# Schematic.net
KiCad netlist of a schematic drawn in EAGLE
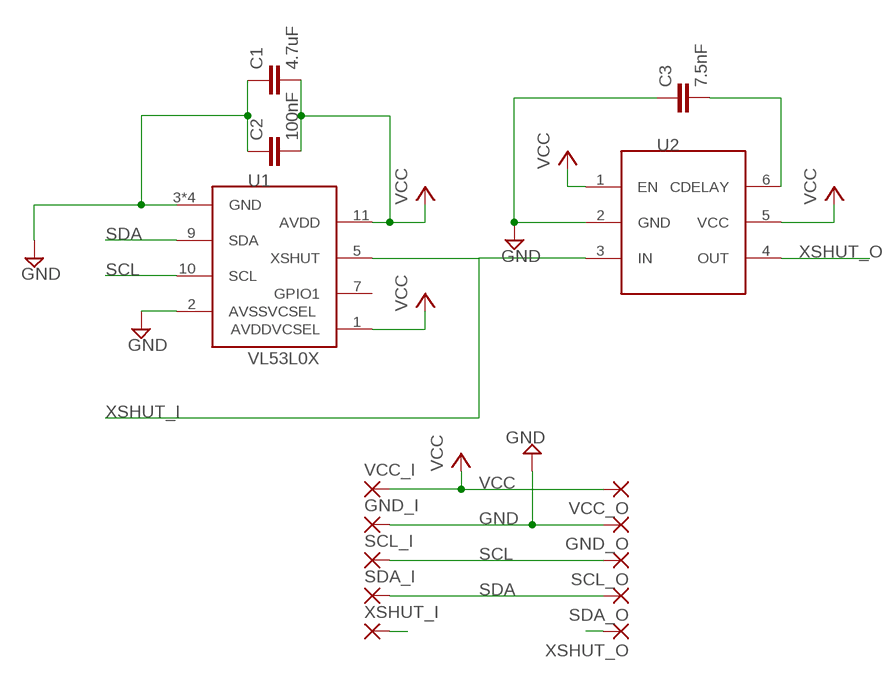
[diagram p0: schematic, sheet 1]

(export (version "E")
  (design (tool "Eeschema 10.0.6"))
  (components
    (comp (ref "C1")
      (value "4.7uF")
      (footprint "eagle-import:0603")
      (libsource (lib "eagle-import") (part "4.7UF0603"))
    )
    (comp (ref "C2")
      (value "100nF")
      (footprint "eagle-import:0603")
      (libsource (lib "eagle-import") (part "0.1UF-0603-25V-5%"))
    )
    (comp (ref "C3")
      (value "7.5nF")
      (footprint "eagle-import:0402")
      (libsource (lib "eagle-import") (part "100PF-0402-50V-5%"))
    )
    (comp (ref "GND_I")
      (value "SMD2")
      (footprint "eagle-import:SMD1,27-2,54")
      (libsource (lib "eagle-import") (part "SMD2"))
    )
    (comp (ref "GND_O")
      (value "SMD2")
      (footprint "eagle-import:SMD1,27-2,54")
      (libsource (lib "eagle-import") (part "SMD2"))
    )
    (comp (ref "SCL_I")
      (value "SMD2")
      (footprint "eagle-import:SMD1,27-2,54")
      (libsource (lib "eagle-import") (part "SMD2"))
    )
    (comp (ref "SCL_O")
      (value "SMD2")
      (footprint "eagle-import:SMD1,27-2,54")
      (libsource (lib "eagle-import") (part "SMD2"))
    )
    (comp (ref "SDA_I")
      (value "SMD2")
      (footprint "eagle-import:SMD1,27-2,54")
      (libsource (lib "eagle-import") (part "SMD2"))
    )
    (comp (ref "SDA_O")
      (value "SMD2")
      (footprint "eagle-import:SMD1,27-2,54")
      (libsource (lib "eagle-import") (part "SMD2"))
    )
    (comp (ref "U1")
      (value "VL53L0X")
      (footprint "eagle-import:OPTICAL_LGA12")
      (libsource (lib "eagle-import") (part "VL53L0X"))
    )
    (comp (ref "U2")
      (value "MAX6895AAZT+T")
      (footprint "eagle-import:6-THIN-SOT23")
      (libsource (lib "eagle-import") (part "MAX6895AAZT+T"))
    )
    (comp (ref "VCC_I")
      (value "SMD2")
      (footprint "eagle-import:SMD1,27-2,54")
      (libsource (lib "eagle-import") (part "SMD2"))
    )
    (comp (ref "VCC_O")
      (value "SMD2")
      (footprint "eagle-import:SMD1,27-2,54")
      (libsource (lib "eagle-import") (part "SMD2"))
    )
    (comp (ref "XSHUT_I")
      (value "SMD2")
      (footprint "eagle-import:SMD1,27-2,54")
      (libsource (lib "eagle-import") (part "SMD2"))
    )
    (comp (ref "XSHUT_O")
      (value "SMD2")
      (footprint "eagle-import:SMD1,27-2,54")
      (libsource (lib "eagle-import") (part "SMD2"))
    )
  )
  (nets
    (net (code "1") (name "/SCL") (class "Default")
      (node (ref "SCL_I") (pin "1") (pinfunction "P_1") (pintype "passive"))
      (node (ref "SCL_O") (pin "1") (pinfunction "P_1") (pintype "passive"))
      (node (ref "U1") (pin "10") (pinfunction "SCL_10") (pintype "bidirectional"))
    )
    (net (code "2") (name "/SDA") (class "Default")
      (node (ref "SDA_I") (pin "1") (pinfunction "P_1") (pintype "passive"))
      (node (ref "SDA_O") (pin "1") (pinfunction "P_1") (pintype "passive"))
      (node (ref "U1") (pin "9") (pinfunction "SDA_9") (pintype "bidirectional"))
    )
    (net (code "3") (name "/XSHUT_I") (class "Default")
      (node (ref "U1") (pin "5") (pinfunction "XSHUT_5") (pintype "bidirectional"))
      (node (ref "U2") (pin "3") (pinfunction "IN_3") (pintype "bidirectional"))
      (node (ref "XSHUT_I") (pin "1") (pinfunction "P_1") (pintype "passive"))
    )
    (net (code "4") (name "/XSHUT_O") (class "Default")
      (node (ref "U2") (pin "4") (pinfunction "OUT_4") (pintype "bidirectional"))
      (node (ref "XSHUT_O") (pin "1") (pinfunction "P_1") (pintype "passive"))
    )
    (net (code "5") (name "GND") (class "Default")
      (node (ref "C1") (pin "1") (pinfunction "1_1") (pintype "passive"))
      (node (ref "C2") (pin "1") (pinfunction "1_1") (pintype "passive"))
      (node (ref "C3") (pin "1") (pinfunction "1_1") (pintype "passive"))
      (node (ref "GND_I") (pin "1") (pinfunction "P_1") (pintype "passive"))
      (node (ref "GND_O") (pin "1") (pinfunction "P_1") (pintype "passive"))
      (node (ref "U1") (pin "12") (pinfunction "GND_12") (pintype "power_in"))
      (node (ref "U1") (pin "2") (pinfunction "AVSSVCSEL_2") (pintype "power_in"))
      (node (ref "U1") (pin "3") (pinfunction "GND_3") (pintype "power_in"))
      (node (ref "U1") (pin "4") (pinfunction "GND_4") (pintype "power_in"))
      (node (ref "U1") (pin "6") (pinfunction "GND_6") (pintype "power_in"))
      (node (ref "U2") (pin "2") (pinfunction "GND_2") (pintype "power_in"))
    )
    (net (code "6") (name "Net-(U2-CDELAY)") (class "Default")
      (node (ref "C3") (pin "2") (pinfunction "2_2") (pintype "passive"))
      (node (ref "U2") (pin "6") (pinfunction "CDELAY_6") (pintype "bidirectional"))
    )
    (net (code "7") (name "VCC") (class "Default")
      (node (ref "C1") (pin "2") (pinfunction "2_2") (pintype "passive"))
      (node (ref "C2") (pin "2") (pinfunction "2_2") (pintype "passive"))
      (node (ref "U1") (pin "1") (pinfunction "AVDDVCSEL_1") (pintype "power_in"))
      (node (ref "U1") (pin "11") (pinfunction "AVDD_11") (pintype "power_in"))
      (node (ref "U2") (pin "1") (pinfunction "EN_1") (pintype "bidirectional"))
      (node (ref "U2") (pin "5") (pinfunction "VCC_5") (pintype "power_in"))
      (node (ref "VCC_I") (pin "1") (pinfunction "P_1") (pintype "passive"))
      (node (ref "VCC_O") (pin "1") (pinfunction "P_1") (pintype "passive"))
    )
    (net (code "8") (name "unconnected-(U1-GPIO1-Pad7)") (class "Default")
      (node (ref "U1") (pin "7") (pinfunction "GPIO1_7") (pintype "bidirectional"))
    )
  )
)
